# ledui.net
KiCad netlist of a schematic drawn in EAGLE
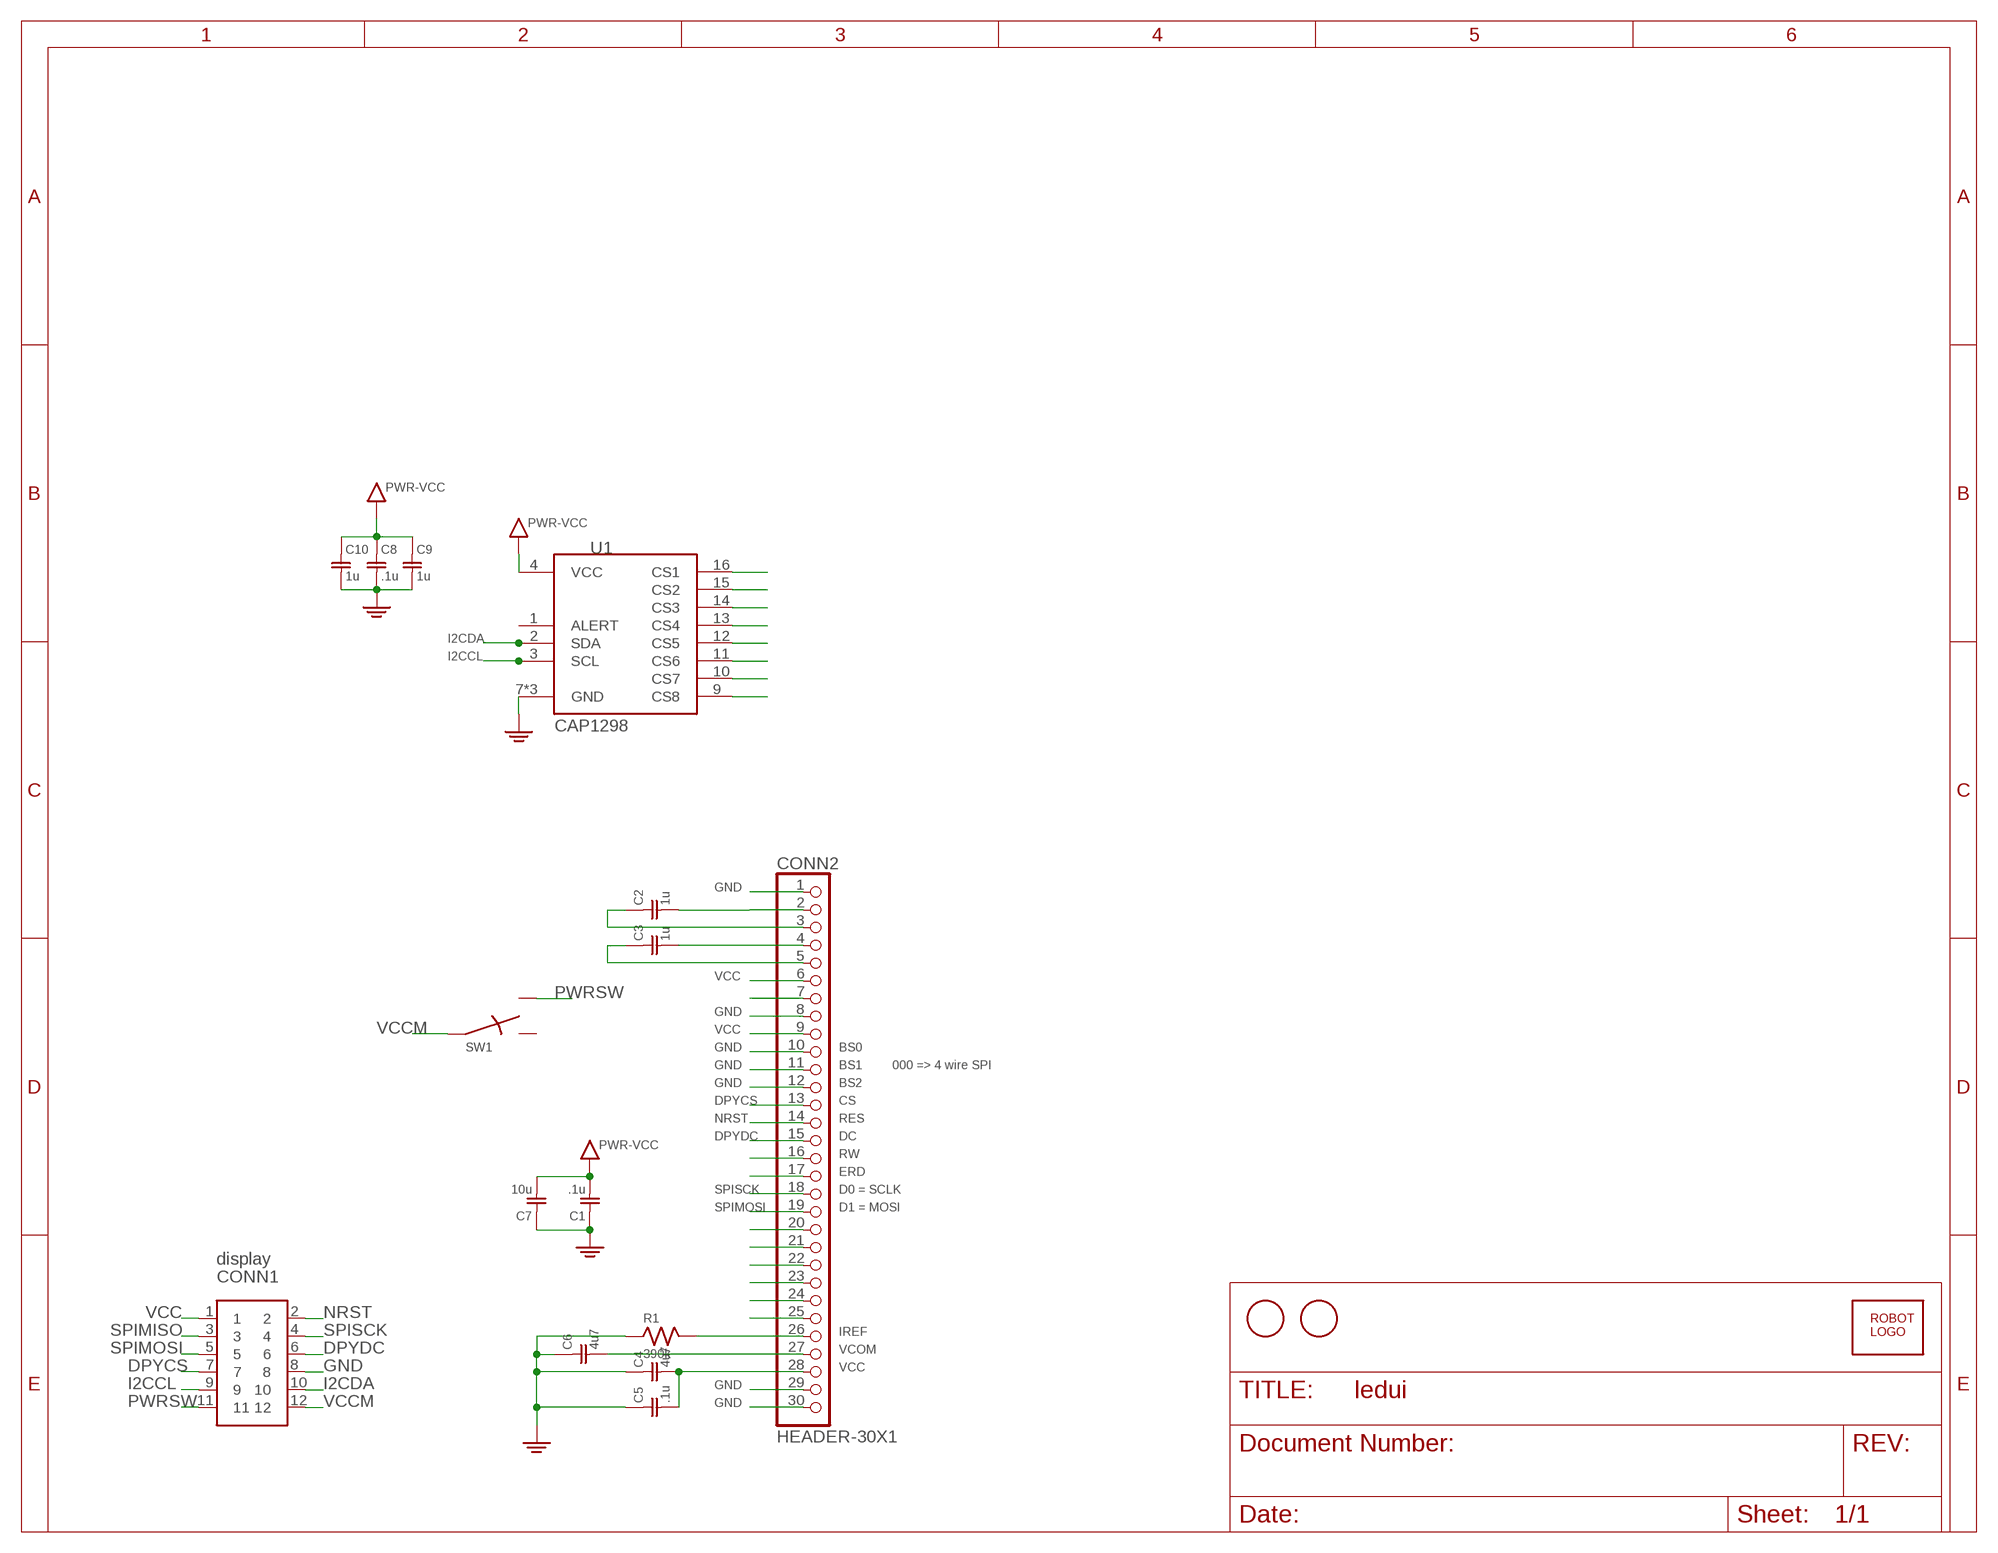
[diagram p0: schematic, sheet 1]

(export (version "E")
  (design (tool "Eeschema 10.0.6"))
  (components
    (comp (ref "C1")
      (value ".1u")
      (footprint "eagle-import:SMD0603")
      (libsource (lib "eagle-import") (part "C0603"))
    )
    (comp (ref "C2")
      (value "1u")
      (footprint "eagle-import:SMD0603")
      (libsource (lib "eagle-import") (part "C0603"))
    )
    (comp (ref "C3")
      (value "1u")
      (footprint "eagle-import:SMD0603")
      (libsource (lib "eagle-import") (part "C0603"))
    )
    (comp (ref "C4")
      (value "4u7")
      (footprint "eagle-import:SMD0603")
      (libsource (lib "eagle-import") (part "C0603"))
    )
    (comp (ref "C5")
      (value ".1u")
      (footprint "eagle-import:SMD0603")
      (libsource (lib "eagle-import") (part "C0603"))
    )
    (comp (ref "C6")
      (value "4u7")
      (footprint "eagle-import:SMD0603")
      (libsource (lib "eagle-import") (part "C0603"))
    )
    (comp (ref "C7")
      (value "10u")
      (footprint "eagle-import:SMD0603")
      (libsource (lib "eagle-import") (part "C0603"))
    )
    (comp (ref "C8")
      (value ".1u")
      (footprint "eagle-import:SMD0603")
      (libsource (lib "eagle-import") (part "C0603"))
    )
    (comp (ref "C9")
      (value "1u")
      (footprint "eagle-import:SMD0603")
      (libsource (lib "eagle-import") (part "C0603"))
    )
    (comp (ref "C10")
      (value "1u")
      (footprint "eagle-import:SMD0603")
      (libsource (lib "eagle-import") (part "C0603"))
    )
    (comp (ref "CONN1")
      (value "HEADER-6X2-PTH")
      (footprint "eagle-import:HEADER-6X2-PTH")
      (libsource (lib "eagle-import") (part "HEADER-6X2-PTH"))
    )
    (comp (ref "CONN2")
      (value "HEADER-30X1")
      (footprint "eagle-import:HEADER-30X1-SMD7")
      (libsource (lib "eagle-import") (part "HEADER-30X1"))
    )
    (comp (ref "R1")
      (value "390k")
      (footprint "eagle-import:SMD0603")
      (libsource (lib "eagle-import") (part "R0603"))
    )
    (comp (ref "SW1")
      (value "SWITCH-SPDT")
      (footprint "eagle-import:ALPS-SSAJ120100")
      (libsource (lib "eagle-import") (part "SWITCH-SPDT"))
    )
    (comp (ref "U$1")
      (value "FIDUCIAL")
      (footprint "eagle-import:FIDUCIAL_1MM")
      (libsource (lib "eagle-import") (part "FIDUCIAL"))
    )
    (comp (ref "U$2")
      (value "FIDUCIAL")
      (footprint "eagle-import:FIDUCIAL_1MM")
      (libsource (lib "eagle-import") (part "FIDUCIAL"))
    )
    (comp (ref "U$3")
      (value "ROBOTMAN-LOGO")
      (footprint "eagle-import:ROBOTMAN-LOGO")
      (libsource (lib "eagle-import") (part "ROBOTMAN-LOGO"))
    )
    (comp (ref "U1")
      (value "CAP1298")
      (footprint "eagle-import:QFN16EP")
      (libsource (lib "eagle-import") (part "CAP1298"))
    )
  )
  (nets
    (net (code "1") (name "/DPYCS") (class "Default")
      (node (ref "CONN1") (pin "7") (pinfunction "7_7") (pintype "bidirectional"))
      (node (ref "CONN2") (pin "13") (pinfunction "13_13") (pintype "passive"))
    )
    (net (code "2") (name "/DPYDC") (class "Default")
      (node (ref "CONN1") (pin "6") (pinfunction "6_6") (pintype "bidirectional"))
      (node (ref "CONN2") (pin "15") (pinfunction "15_15") (pintype "passive"))
    )
    (net (code "3") (name "/I2CCL") (class "Default")
      (node (ref "CONN1") (pin "9") (pinfunction "9_9") (pintype "bidirectional"))
      (node (ref "U1") (pin "3") (pinfunction "SCL_3") (pintype "bidirectional"))
    )
    (net (code "4") (name "/I2CDA") (class "Default")
      (node (ref "CONN1") (pin "10") (pinfunction "10_10") (pintype "bidirectional"))
      (node (ref "U1") (pin "2") (pinfunction "SDA_2") (pintype "bidirectional"))
    )
    (net (code "5") (name "/NRST") (class "Default")
      (node (ref "CONN1") (pin "2") (pinfunction "2_2") (pintype "bidirectional"))
      (node (ref "CONN2") (pin "14") (pinfunction "14_14") (pintype "passive"))
    )
    (net (code "6") (name "/PWRSW") (class "Default")
      (node (ref "CONN1") (pin "11") (pinfunction "11_11") (pintype "bidirectional"))
      (node (ref "SW1") (pin "2") (pinfunction "P$3_2") (pintype "passive"))
    )
    (net (code "7") (name "/SPIMISO") (class "Default")
      (node (ref "CONN1") (pin "3") (pinfunction "3_3") (pintype "bidirectional"))
    )
    (net (code "8") (name "/SPIMOSI") (class "Default")
      (node (ref "CONN1") (pin "5") (pinfunction "5_5") (pintype "bidirectional"))
      (node (ref "CONN2") (pin "19") (pinfunction "19_19") (pintype "passive"))
    )
    (net (code "9") (name "/SPISCK") (class "Default")
      (node (ref "CONN1") (pin "4") (pinfunction "4_4") (pintype "bidirectional"))
      (node (ref "CONN2") (pin "18") (pinfunction "18_18") (pintype "passive"))
    )
    (net (code "10") (name "/VCCM") (class "Default")
      (node (ref "CONN1") (pin "12") (pinfunction "12_12") (pintype "bidirectional"))
      (node (ref "SW1") (pin "C") (pinfunction "C_C") (pintype "passive"))
    )
    (net (code "11") (name "Net-(C2-P$1)") (class "Default")
      (node (ref "C2") (pin "1") (pinfunction "P$1_1") (pintype "passive"))
      (node (ref "CONN2") (pin "3") (pinfunction "3_3") (pintype "passive"))
    )
    (net (code "12") (name "Net-(C2-P$2)") (class "Default")
      (node (ref "C2") (pin "2") (pinfunction "P$2_2") (pintype "passive"))
      (node (ref "CONN2") (pin "2") (pinfunction "2_2") (pintype "passive"))
    )
    (net (code "13") (name "Net-(C3-P$1)") (class "Default")
      (node (ref "C3") (pin "1") (pinfunction "P$1_1") (pintype "passive"))
      (node (ref "CONN2") (pin "5") (pinfunction "5_5") (pintype "passive"))
    )
    (net (code "14") (name "Net-(C3-P$2)") (class "Default")
      (node (ref "C3") (pin "2") (pinfunction "P$2_2") (pintype "passive"))
      (node (ref "CONN2") (pin "4") (pinfunction "4_4") (pintype "passive"))
    )
    (net (code "15") (name "Net-(C4-P$2)") (class "Default")
      (node (ref "C4") (pin "2") (pinfunction "P$2_2") (pintype "passive"))
      (node (ref "C5") (pin "2") (pinfunction "P$2_2") (pintype "passive"))
      (node (ref "CONN2") (pin "28") (pinfunction "28_28") (pintype "passive"))
    )
    (net (code "16") (name "Net-(C6-P$2)") (class "Default")
      (node (ref "C6") (pin "2") (pinfunction "P$2_2") (pintype "passive"))
      (node (ref "CONN2") (pin "27") (pinfunction "27_27") (pintype "passive"))
    )
    (net (code "17") (name "Net-(R1-P$2)") (class "Default")
      (node (ref "CONN2") (pin "26") (pinfunction "26_26") (pintype "passive"))
      (node (ref "R1") (pin "2") (pinfunction "P$2_2") (pintype "passive"))
    )
    (net (code "18") (name "PWR-GND") (class "Default")
      (node (ref "C1") (pin "1") (pinfunction "P$1_1") (pintype "passive"))
      (node (ref "C10") (pin "2") (pinfunction "P$2_2") (pintype "passive"))
      (node (ref "C4") (pin "1") (pinfunction "P$1_1") (pintype "passive"))
      (node (ref "C5") (pin "1") (pinfunction "P$1_1") (pintype "passive"))
      (node (ref "C6") (pin "1") (pinfunction "P$1_1") (pintype "passive"))
      (node (ref "C7") (pin "1") (pinfunction "P$1_1") (pintype "passive"))
      (node (ref "C8") (pin "2") (pinfunction "P$2_2") (pintype "passive"))
      (node (ref "C9") (pin "2") (pinfunction "P$2_2") (pintype "passive"))
      (node (ref "CONN1") (pin "8") (pinfunction "8_8") (pintype "bidirectional"))
      (node (ref "CONN2") (pin "1") (pinfunction "1_1") (pintype "passive"))
      (node (ref "CONN2") (pin "10") (pinfunction "10_10") (pintype "passive"))
      (node (ref "CONN2") (pin "11") (pinfunction "11_11") (pintype "passive"))
      (node (ref "CONN2") (pin "12") (pinfunction "12_12") (pintype "passive"))
      (node (ref "CONN2") (pin "29") (pinfunction "29_29") (pintype "passive"))
      (node (ref "CONN2") (pin "30") (pinfunction "30_30") (pintype "passive"))
      (node (ref "CONN2") (pin "8") (pinfunction "8_8") (pintype "passive"))
      (node (ref "R1") (pin "1") (pinfunction "P$1_1") (pintype "passive"))
      (node (ref "U1") (pin "7") (pinfunction "GND_7") (pintype "bidirectional"))
      (node (ref "U1") (pin "8") (pinfunction "GND_8") (pintype "bidirectional"))
      (node (ref "U1") (pin "P$1") (pinfunction "GND_P$1") (pintype "bidirectional"))
    )
    (net (code "19") (name "PWR-VCC") (class "Default")
      (node (ref "C1") (pin "2") (pinfunction "P$2_2") (pintype "passive"))
      (node (ref "C10") (pin "1") (pinfunction "P$1_1") (pintype "passive"))
      (node (ref "C7") (pin "2") (pinfunction "P$2_2") (pintype "passive"))
      (node (ref "C8") (pin "1") (pinfunction "P$1_1") (pintype "passive"))
      (node (ref "C9") (pin "1") (pinfunction "P$1_1") (pintype "passive"))
      (node (ref "CONN1") (pin "1") (pinfunction "1_1") (pintype "bidirectional"))
      (node (ref "CONN2") (pin "6") (pinfunction "6_6") (pintype "passive"))
      (node (ref "CONN2") (pin "9") (pinfunction "9_9") (pintype "passive"))
      (node (ref "U1") (pin "4") (pinfunction "VCC_4") (pintype "bidirectional"))
    )
    (net (code "20") (name "unconnected-(CONN2-Pad7)") (class "Default")
      (node (ref "CONN2") (pin "7") (pinfunction "7_7") (pintype "passive"))
    )
    (net (code "21") (name "unconnected-(CONN2-Pad16)") (class "Default")
      (node (ref "CONN2") (pin "16") (pinfunction "16_16") (pintype "passive"))
    )
    (net (code "22") (name "unconnected-(CONN2-Pad17)") (class "Default")
      (node (ref "CONN2") (pin "17") (pinfunction "17_17") (pintype "passive"))
    )
    (net (code "23") (name "unconnected-(CONN2-Pad20)") (class "Default")
      (node (ref "CONN2") (pin "20") (pinfunction "20_20") (pintype "passive"))
    )
    (net (code "24") (name "unconnected-(CONN2-Pad21)") (class "Default")
      (node (ref "CONN2") (pin "21") (pinfunction "21_21") (pintype "passive"))
    )
    (net (code "25") (name "unconnected-(CONN2-Pad22)") (class "Default")
      (node (ref "CONN2") (pin "22") (pinfunction "22_22") (pintype "passive"))
    )
    (net (code "26") (name "unconnected-(CONN2-Pad23)") (class "Default")
      (node (ref "CONN2") (pin "23") (pinfunction "23_23") (pintype "passive"))
    )
    (net (code "27") (name "unconnected-(CONN2-Pad24)") (class "Default")
      (node (ref "CONN2") (pin "24") (pinfunction "24_24") (pintype "passive"))
    )
    (net (code "28") (name "unconnected-(CONN2-Pad25)") (class "Default")
      (node (ref "CONN2") (pin "25") (pinfunction "25_25") (pintype "passive"))
    )
    (net (code "29") (name "unconnected-(SW1-P$2-Pad1)") (class "Default")
      (node (ref "SW1") (pin "1") (pinfunction "P$2_1") (pintype "passive"))
    )
    (net (code "30") (name "unconnected-(U1-ALERT-Pad1)") (class "Default")
      (node (ref "U1") (pin "1") (pinfunction "ALERT_1") (pintype "bidirectional"))
    )
    (net (code "31") (name "unconnected-(U1-CS1-Pad16)") (class "Default")
      (node (ref "U1") (pin "16") (pinfunction "CS1_16") (pintype "bidirectional"))
    )
    (net (code "32") (name "unconnected-(U1-CS2-Pad15)") (class "Default")
      (node (ref "U1") (pin "15") (pinfunction "CS2_15") (pintype "bidirectional"))
    )
    (net (code "33") (name "unconnected-(U1-CS3-Pad14)") (class "Default")
      (node (ref "U1") (pin "14") (pinfunction "CS3_14") (pintype "bidirectional"))
    )
    (net (code "34") (name "unconnected-(U1-CS4-Pad13)") (class "Default")
      (node (ref "U1") (pin "13") (pinfunction "CS4_13") (pintype "bidirectional"))
    )
    (net (code "35") (name "unconnected-(U1-CS5-Pad12)") (class "Default")
      (node (ref "U1") (pin "12") (pinfunction "CS5_12") (pintype "bidirectional"))
    )
    (net (code "36") (name "unconnected-(U1-CS6-Pad11)") (class "Default")
      (node (ref "U1") (pin "11") (pinfunction "CS6_11") (pintype "bidirectional"))
    )
    (net (code "37") (name "unconnected-(U1-CS7-Pad10)") (class "Default")
      (node (ref "U1") (pin "10") (pinfunction "CS7_10") (pintype "bidirectional"))
    )
    (net (code "38") (name "unconnected-(U1-CS8-Pad9)") (class "Default")
      (node (ref "U1") (pin "9") (pinfunction "CS8_9") (pintype "bidirectional"))
    )
  )
)
